# Sheet1.net
KiCad netlist of a schematic drawn in Altium Designer
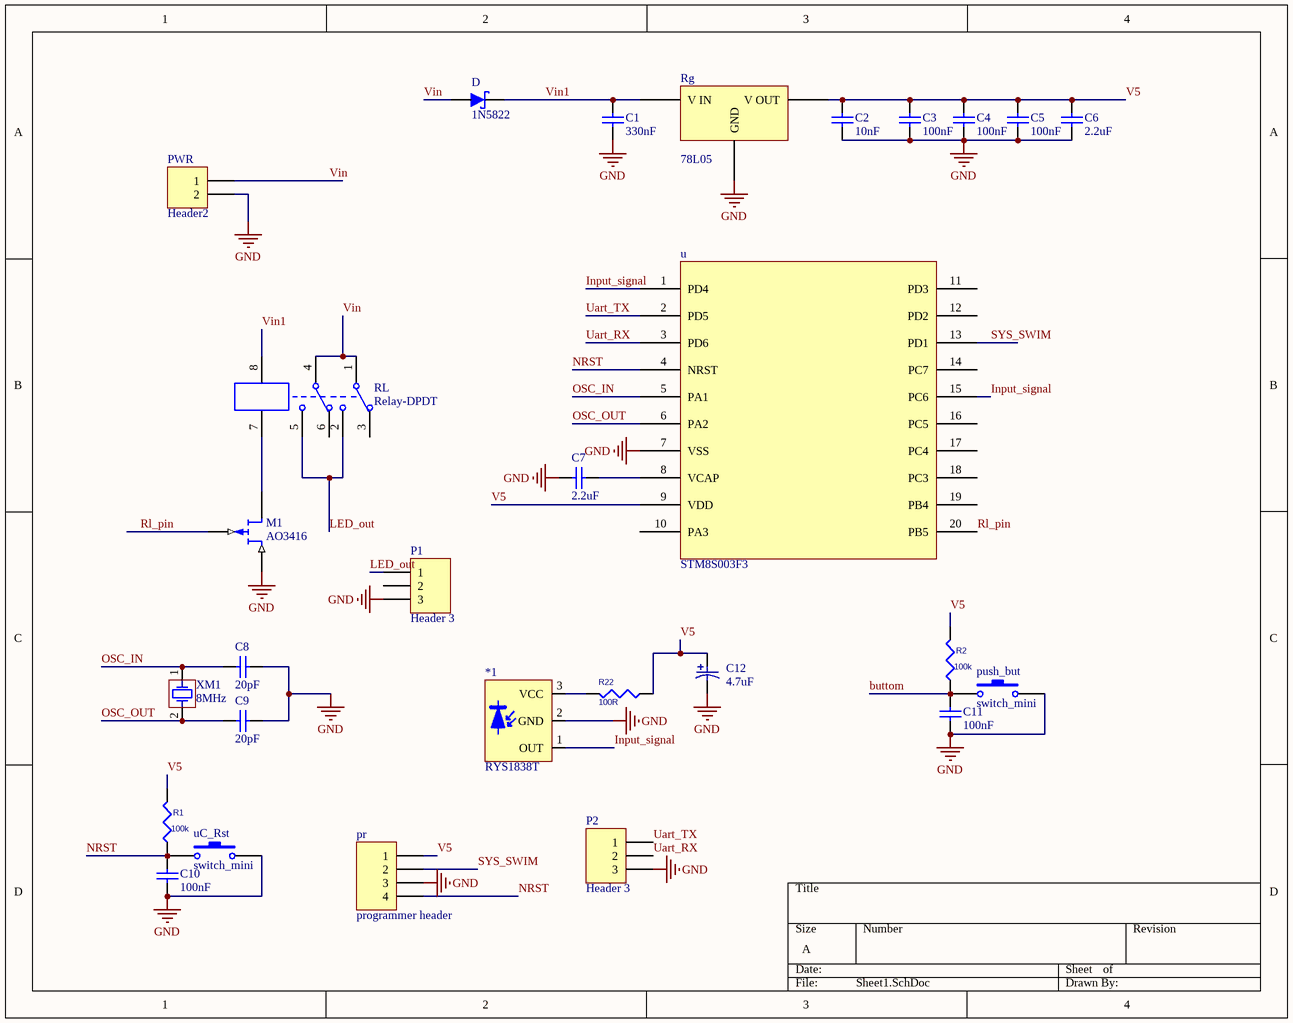
[diagram p0: Sheet1.SchDoc]

(export (version "E")
  (design (tool "Eeschema 10.0.6"))
  (components
    (comp (ref "*1")
      (value "RYS1838T")
      (footprint "RYS1838T")
      (libsource (lib "NAHAL_LIB") (part "RYS1838T"))
    )
    (comp (ref "C1")
      (value "330nF")
      (footprint "1206C")
      (description "Capacitor")
      (libsource (lib "Fanavard95") (part "Cap"))
    )
    (comp (ref "C2")
      (value "10nF")
      (footprint "1206C")
      (description "Capacitor")
      (libsource (lib "Fanavard95") (part "Cap"))
    )
    (comp (ref "C3")
      (value "100nF")
      (footprint "1206C")
      (description "Capacitor")
      (libsource (lib "NAHAL_LIB") (part "Cap"))
    )
    (comp (ref "C4")
      (value "100nF")
      (footprint "1206C")
      (description "Capacitor")
      (libsource (lib "NAHAL_LIB") (part "Cap"))
    )
    (comp (ref "C5")
      (value "100nF")
      (footprint "1206C")
      (description "Capacitor")
      (libsource (lib "NAHAL_LIB") (part "Cap"))
    )
    (comp (ref "C6")
      (value "2.2uF")
      (footprint "0805C")
      (description "Capacitor")
      (libsource (lib "NAHAL_LIB") (part "Cap"))
    )
    (comp (ref "C7")
      (value "2.2uF")
      (footprint "0805C")
      (description "Capacitor")
      (libsource (lib "NAHAL_LIB") (part "Cap"))
    )
    (comp (ref "C8")
      (value "20pF")
      (footprint "1206C")
      (description "Capacitor")
      (libsource (lib "NAHAL_LIB") (part "Cap"))
    )
    (comp (ref "C9")
      (value "20pF")
      (footprint "1206C")
      (description "Capacitor")
      (libsource (lib "NAHAL_LIB") (part "Cap"))
    )
    (comp (ref "C10")
      (value "100nF")
      (footprint "1206C")
      (description "Capacitor")
      (libsource (lib "NAHAL_LIB") (part "Cap"))
    )
    (comp (ref "C11")
      (value "100nF")
      (footprint "1206C")
      (description "Capacitor")
      (libsource (lib "NAHAL_LIB") (part "Cap"))
    )
    (comp (ref "C12")
      (value "4.7uF")
      (footprint "SIZE_A")
      (description "Capacitor, Tantalum,")
      (fields (field (name "TOLERANCE") "20%"))
      (libsource (lib "NAHAL_LIB") (part "Cap-Tantal"))
    )
    (comp (ref "D") (value "1N5822") (footprint "430X270D") (libsource (lib "Fanavard95") (part "1N5819")))
    (comp (ref "M1")
      (value "AO3416")
      (footprint "SOT23_3")
      (description "P-Channel MESFET")
      (fields (field (name "PUBLISHER") "Altium Limited"))
      (libsource (lib "Miscellaneous Devices") (part "MESFET-P"))
    )
    (comp (ref "P1")
      (value "Header 3")
      (footprint "HDR1X3")
      (description "Header, 3-Pin")
      (fields (field (name "PUBLISHER") "Altium Limited"))
      (libsource (lib "") (part "Header 3_1"))
    )
    (comp (ref "P2")
      (value "Header 3")
      (footprint "HDR1X3")
      (description "Header, 3-Pin")
      (fields (field (name "PUBLISHER") "Altium Limited"))
      (libsource (lib "Miscellaneous Connectors") (part "Header 3"))
    )
    (comp (ref "pr")
      (value "programmer header")
      (footprint "HEADER_4_JMP")
      (description "Header, 4-Pin")
      (fields (field (name "PUBLISHER") "Altium Limited"))
      (libsource (lib "Fanavard95") (part "Header 4"))
    )
    (comp (ref "push_but")
      (value "switch_mini")
      (footprint "switch_mini_smd")
      (libsource (lib "NAHAL_LIB") (part "switch_mini"))
    )
    (comp (ref "PWR")
      (value "Header2")
      (footprint "COMM HEADER 2")
      (description "Header, 2-Pin")
      (fields (field (name "PUBLISHER") "Altium Limited"))
      (libsource (lib "Fanavard95") (part "Header 2"))
    )
    (comp (ref "R1") (value "100k") (footprint "0805L") (libsource (lib "NAHAL_LIB") (part "R")))
    (comp (ref "R2") (value "100k") (footprint "0805L") (libsource (lib "NAHAL_LIB") (part "R")))
    (comp (ref "R22") (value "100R") (footprint "0805L") (libsource (lib "NAHAL_LIB") (part "R")))
    (comp (ref "Rg")
      (value "78L05")
      (footprint "SOT-89")
      (description "Voltage Regulator")
      (libsource (lib "iDr.ALTIUM2D") (part "78LXX"))
    )
    (comp (ref "RL")
      (value "Relay-DPDT")
      (footprint "RELAY-DPDT-1")
      (description "Dual-Pole Dual-Throw Relay")
      (fields (field (name "PUBLISHER") "Altium Limited"))
      (libsource (lib "iDr.ALTIUM(www.idrdot.ir)") (part "Relay-DPDT"))
    )
    (comp (ref "u")
      (value "STM8S003F3")
      (footprint "TSSOP20_L")
      (libsource (lib "Schlib1") (part "Component_1"))
    )
    (comp (ref "uC_Rst")
      (value "switch_mini")
      (footprint "switch_mini_smd")
      (libsource (lib "NAHAL_LIB") (part "switch_mini"))
    )
    (comp (ref "XM1") (value "8MHz") (footprint "XTLT_2") (libsource (lib "NAHAL_LIB") (part "XTAL")))
  )
  (nets
    (net (code "1") (name "/Input_signal") (class "Default")
      (node (ref "*1") (pin "1") (pinfunction "OUT_1") (pintype "passive"))
      (node (ref "u") (pin "1") (pinfunction "PD4_1") (pintype "passive"))
      (node (ref "u") (pin "15") (pinfunction "PC6_15") (pintype "passive"))
    )
    (net (code "2") (name "/LED_out") (class "Default")
      (node (ref "P1") (pin "1") (pinfunction "1_1") (pintype "passive"))
      (node (ref "RL") (pin "2") (pinfunction "2_2") (pintype "passive"))
      (node (ref "RL") (pin "5") (pinfunction "5_5") (pintype "passive"))
    )
    (net (code "3") (name "/NRST") (class "Default")
      (node (ref "C10") (pin "2") (pinfunction "2_2") (pintype "passive"))
      (node (ref "R1") (pin "1") (pinfunction "1_1") (pintype "passive"))
      (node (ref "pr") (pin "4") (pinfunction "4_4") (pintype "passive"))
      (node (ref "u") (pin "4") (pinfunction "NRST_4") (pintype "passive"))
      (node (ref "uC_Rst") (pin "1") (pinfunction "1_1") (pintype "passive"))
    )
    (net (code "4") (name "/OSC_IN") (class "Default")
      (node (ref "C8") (pin "1") (pinfunction "1_1") (pintype "passive"))
      (node (ref "XM1") (pin "1") (pinfunction "OSC1_1") (pintype "passive"))
      (node (ref "u") (pin "5") (pinfunction "PA1_5") (pintype "passive"))
    )
    (net (code "5") (name "/OSC_OUT") (class "Default")
      (node (ref "C9") (pin "1") (pinfunction "1_1") (pintype "passive"))
      (node (ref "XM1") (pin "2") (pinfunction "OSC2_2") (pintype "passive"))
      (node (ref "u") (pin "6") (pinfunction "PA2_6") (pintype "passive"))
    )
    (net (code "6") (name "/Rl_pin") (class "Default")
      (node (ref "M1") (pin "2") (pinfunction "G_2") (pintype "input"))
      (node (ref "u") (pin "20") (pinfunction "PB5_20") (pintype "passive"))
    )
    (net (code "7") (name "/SYS_SWIM") (class "Default")
      (node (ref "pr") (pin "2") (pinfunction "2_2") (pintype "passive"))
      (node (ref "u") (pin "13") (pinfunction "PD1_13") (pintype "passive"))
    )
    (net (code "8") (name "/Uart_RX") (class "Default")
      (node (ref "P2") (pin "2") (pinfunction "2_2") (pintype "passive"))
      (node (ref "u") (pin "3") (pinfunction "PD6_3") (pintype "passive"))
    )
    (net (code "9") (name "/Uart_TX") (class "Default")
      (node (ref "P2") (pin "1") (pinfunction "1_1") (pintype "passive"))
      (node (ref "u") (pin "2") (pinfunction "PD5_2") (pintype "passive"))
    )
    (net (code "10") (name "/V5") (class "Default")
      (node (ref "C12") (pin "1") (pinfunction "+_1") (pintype "passive"))
      (node (ref "C2") (pin "1") (pinfunction "1_1") (pintype "passive"))
      (node (ref "C3") (pin "2") (pinfunction "2_2") (pintype "passive"))
      (node (ref "C4") (pin "2") (pinfunction "2_2") (pintype "passive"))
      (node (ref "C5") (pin "2") (pinfunction "2_2") (pintype "passive"))
      (node (ref "C6") (pin "2") (pinfunction "2_2") (pintype "passive"))
      (node (ref "R1") (pin "2") (pinfunction "2_2") (pintype "passive"))
      (node (ref "R2") (pin "2") (pinfunction "2_2") (pintype "passive"))
      (node (ref "R22") (pin "1") (pinfunction "1_1") (pintype "passive"))
      (node (ref "Rg") (pin "1") (pinfunction "V_OUT_1") (pintype "passive"))
      (node (ref "pr") (pin "1") (pinfunction "1_1") (pintype "passive"))
      (node (ref "u") (pin "9") (pinfunction "VDD_9") (pintype "passive"))
    )
    (net (code "11") (name "/Vin") (class "Default")
      (node (ref "D") (pin "1") (pintype "passive"))
      (node (ref "PWR") (pin "1") (pinfunction "1_1") (pintype "passive"))
      (node (ref "RL") (pin "1") (pinfunction "1_1") (pintype "passive"))
      (node (ref "RL") (pin "4") (pinfunction "4_4") (pintype "passive"))
    )
    (net (code "12") (name "/Vin1") (class "Default")
      (node (ref "C1") (pin "1") (pinfunction "1_1") (pintype "passive"))
      (node (ref "D") (pin "2") (pintype "passive"))
      (node (ref "RL") (pin "8") (pinfunction "8_8") (pintype "passive"))
      (node (ref "Rg") (pin "3") (pinfunction "V_IN_3") (pintype "passive"))
    )
    (net (code "13") (name "/buttom") (class "Default")
      (node (ref "C11") (pin "2") (pinfunction "2_2") (pintype "passive"))
      (node (ref "R2") (pin "1") (pinfunction "1_1") (pintype "passive"))
      (node (ref "push_but") (pin "1") (pinfunction "1_1") (pintype "passive"))
    )
    (net (code "14") (name "GND") (class "Default")
      (node (ref "*1") (pin "2") (pinfunction "GND_2") (pintype "passive"))
      (node (ref "C1") (pin "2") (pinfunction "2_2") (pintype "passive"))
      (node (ref "C10") (pin "1") (pinfunction "1_1") (pintype "passive"))
      (node (ref "C11") (pin "1") (pinfunction "1_1") (pintype "passive"))
      (node (ref "C12") (pin "2") (pintype "passive"))
      (node (ref "C2") (pin "2") (pinfunction "2_2") (pintype "passive"))
      (node (ref "C3") (pin "1") (pinfunction "1_1") (pintype "passive"))
      (node (ref "C4") (pin "1") (pinfunction "1_1") (pintype "passive"))
      (node (ref "C5") (pin "1") (pinfunction "1_1") (pintype "passive"))
      (node (ref "C6") (pin "1") (pinfunction "1_1") (pintype "passive"))
      (node (ref "C7") (pin "2") (pinfunction "2_2") (pintype "passive"))
      (node (ref "C8") (pin "2") (pinfunction "2_2") (pintype "passive"))
      (node (ref "C9") (pin "2") (pinfunction "2_2") (pintype "passive"))
      (node (ref "M1") (pin "1") (pinfunction "D_1") (pintype "input"))
      (node (ref "P1") (pin "3") (pinfunction "3_3") (pintype "passive"))
      (node (ref "P2") (pin "3") (pinfunction "3_3") (pintype "passive"))
      (node (ref "PWR") (pin "2") (pinfunction "2_2") (pintype "passive"))
      (node (ref "Rg") (pin "2") (pinfunction "GND_2") (pintype "passive"))
      (node (ref "pr") (pin "3") (pinfunction "3_3") (pintype "passive"))
      (node (ref "push_but") (pin "2") (pinfunction "2_2") (pintype "passive"))
      (node (ref "u") (pin "7") (pinfunction "VSS_7") (pintype "passive"))
      (node (ref "uC_Rst") (pin "2") (pinfunction "2_2") (pintype "passive"))
    )
    (net (code "15") (name "Net-(*1-VCC)") (class "Default")
      (node (ref "*1") (pin "3") (pinfunction "VCC_3") (pintype "passive"))
      (node (ref "R22") (pin "2") (pinfunction "2_2") (pintype "passive"))
    )
    (net (code "16") (name "Net-(M1-S)") (class "Default")
      (node (ref "M1") (pin "3") (pinfunction "S_3") (pintype "passive"))
      (node (ref "RL") (pin "7") (pinfunction "7_7") (pintype "passive"))
    )
    (net (code "17") (name "Net-(u-VCAP)") (class "Default")
      (node (ref "C7") (pin "1") (pinfunction "1_1") (pintype "passive"))
      (node (ref "u") (pin "8") (pinfunction "VCAP_8") (pintype "passive"))
    )
    (net (code "18") (name "unconnected-(P1-Pad2)") (class "Default")
      (node (ref "P1") (pin "2") (pinfunction "2_2") (pintype "passive"))
    )
    (net (code "19") (name "unconnected-(RL-Pad3)") (class "Default")
      (node (ref "RL") (pin "3") (pinfunction "3_3") (pintype "passive"))
    )
    (net (code "20") (name "unconnected-(RL-Pad6)") (class "Default")
      (node (ref "RL") (pin "6") (pinfunction "6_6") (pintype "passive"))
    )
    (net (code "21") (name "unconnected-(u-PA3-Pad10)") (class "Default")
      (node (ref "u") (pin "10") (pinfunction "PA3_10") (pintype "passive"))
    )
    (net (code "22") (name "unconnected-(u-PB4-Pad19)") (class "Default")
      (node (ref "u") (pin "19") (pinfunction "PB4_19") (pintype "passive"))
    )
    (net (code "23") (name "unconnected-(u-PC3-Pad18)") (class "Default")
      (node (ref "u") (pin "18") (pinfunction "PC3_18") (pintype "passive"))
    )
    (net (code "24") (name "unconnected-(u-PC4-Pad17)") (class "Default")
      (node (ref "u") (pin "17") (pinfunction "PC4_17") (pintype "passive"))
    )
    (net (code "25") (name "unconnected-(u-PC5-Pad16)") (class "Default")
      (node (ref "u") (pin "16") (pinfunction "PC5_16") (pintype "passive"))
    )
    (net (code "26") (name "unconnected-(u-PC7-Pad14)") (class "Default")
      (node (ref "u") (pin "14") (pinfunction "PC7_14") (pintype "passive"))
    )
    (net (code "27") (name "unconnected-(u-PD2-Pad12)") (class "Default")
      (node (ref "u") (pin "12") (pinfunction "PD2_12") (pintype "passive"))
    )
    (net (code "28") (name "unconnected-(u-PD3-Pad11)") (class "Default")
      (node (ref "u") (pin "11") (pinfunction "PD3_11") (pintype "passive"))
    )
  )
)
